# Main.net
KiCad netlist of a schematic drawn in Altium Designer
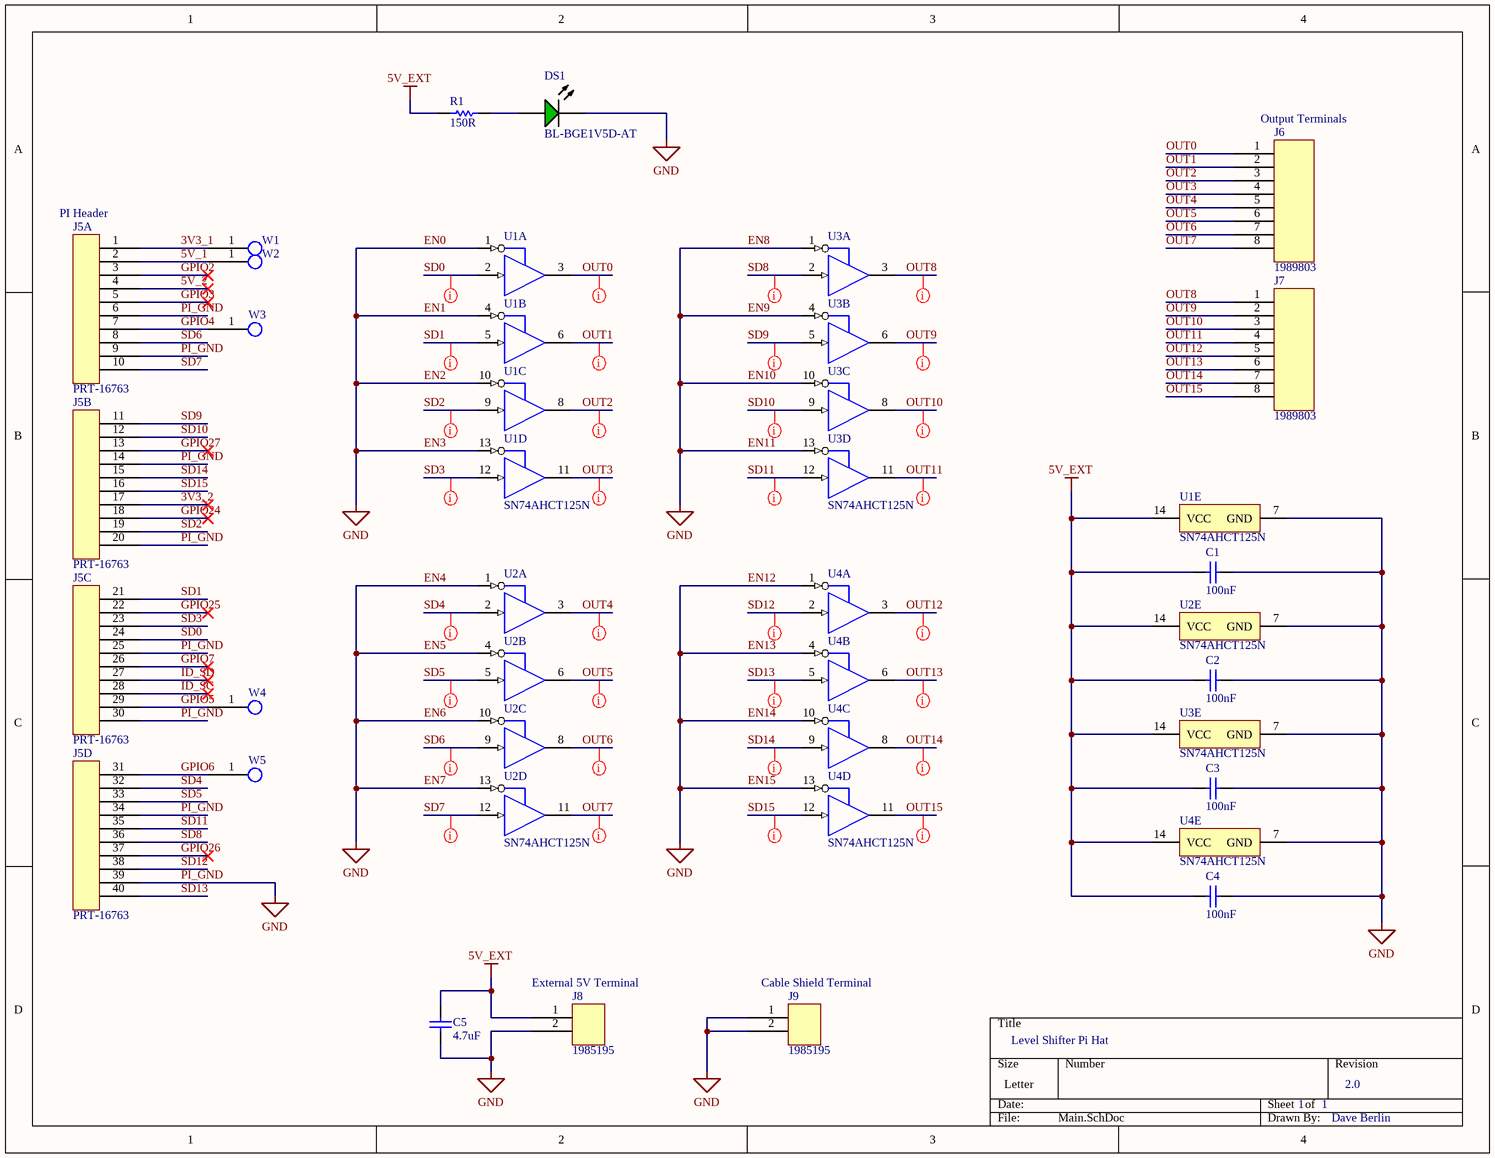
[diagram p0: Main.SchDoc]

(export (version "E")
  (design (tool "Eeschema 10.0.6"))
  (components
    (comp (ref "C1")
      (value "100nF")
      (footprint "FP-CL21-IPC_A")
      (description "CAP CER 0.1UF 50V X7R 0805")
      (fields (field (name "VOLTAGE") "50V") (field (name "TOLERANCE") "10%"))
      (libsource (lib "University of Colorado Boulder") (part "CAP"))
    )
    (comp (ref "C2")
      (value "100nF")
      (footprint "FP-CL21-IPC_A")
      (description "CAP CER 0.1UF 50V X7R 0805")
      (fields (field (name "VOLTAGE") "50V") (field (name "TOLERANCE") "10%"))
      (libsource (lib "University of Colorado Boulder") (part "CAP"))
    )
    (comp (ref "C3")
      (value "100nF")
      (footprint "FP-CL21-IPC_A")
      (description "CAP CER 0.1UF 50V X7R 0805")
      (fields (field (name "VOLTAGE") "50V") (field (name "TOLERANCE") "10%"))
      (libsource (lib "University of Colorado Boulder") (part "CAP"))
    )
    (comp (ref "C4")
      (value "100nF")
      (footprint "FP-CL21-IPC_A")
      (description "CAP CER 0.1UF 50V X7R 0805")
      (fields (field (name "VOLTAGE") "50V") (field (name "TOLERANCE") "10%"))
      (libsource (lib "University of Colorado Boulder") (part "CAP"))
    )
    (comp (ref "C5")
      (value "4.7uF")
      (footprint "FP-CL21-IPC_A")
      (description "CAP CER 4.7UF 25V X5R 0805")
      (fields (field (name "TOLERANCE") "10%") (field (name "Comment") "CL21A475KAQNNNE"))
      (libsource (lib "University of Colorado Boulder") (part "CAP"))
    )
    (comp (ref "DS1")
      (value "BL-BGE1V5D-AT")
      (footprint "LED-2P-2.54-3MM")
      (description "LED Green, 80 mW, 30 mA Max, 200 mcd at 20 mA-40 to 85 degC, 2-Pin THD, RoHS, Bulk")
      (fields (field (name "POWER") "80mW"))
      (libsource (lib "University of Colorado Boulder") (part "LED-GREEN-AK-2"))
    )
    (comp (ref "J5")
      (value "PRT-16763")
      (footprint "PRT-16763-Footprint-1")
      (description "Extended GPIO Female Header - 2x20 Pin (16mm/7.30mm)")
      (libsource (lib "University of Colorado Boulder") (part "PRT-16764-Symbol"))
    )
    (comp (ref "J6")
      (value "1989803")
      (footprint "CONN_1989803_PXC")
      (description "Conn PC Terminal Block 8 POS 2.5mm Solder Thru-Hole 2A")
      (fields (field (name "VOLTAGE") "300V"))
      (libsource (lib "University of Colorado Boulder") (part "Connector-Generic-8-Position"))
    )
    (comp (ref "J7")
      (value "1989803")
      (footprint "CONN_1989803_PXC")
      (description "Conn PC Terminal Block 8 POS 2.5mm Solder Thru-Hole 2A")
      (fields (field (name "VOLTAGE") "300V"))
      (libsource (lib "University of Colorado Boulder") (part "Connector-Generic-8-Position"))
    )
    (comp (ref "J8")
      (value "1985195")
      (footprint "CONN_1985195_PXC")
      (description "Conn PC Terminal Block 2 POS 3.5mm Solder Thru-Hole 8A Cardboard")
      (fields (field (name "VOLTAGE") "300V"))
      (libsource (lib "University of Colorado Boulder") (part "1985195-Symbol-1"))
    )
    (comp (ref "J9")
      (value "1985195")
      (footprint "CONN_1985195_PXC")
      (description "Conn PC Terminal Block 2 POS 3.5mm Solder Thru-Hole 8A Cardboard")
      (fields (field (name "VOLTAGE") "300V"))
      (libsource (lib "University of Colorado Boulder") (part "1985195-Symbol-1"))
    )
    (comp (ref "R1")
      (value "150R")
      (footprint "STA_CF14_STP")
      (description "CF Series 0.25 W 150 Ohm ±5 % 0 to -400 ppm/°C Through Hole Carbon Film Resistor")
      (fields (field (name "TOLERANCE") "5%") (field (name "Comment") "CF14JT150R"))
      (libsource (lib "University of Colorado Boulder") (part "RES"))
    )
    (comp (ref "U1")
      (value "SN74AHCT125N")
      (footprint "N0014A")
      (description "Buffer/Line Driver 4-CH Non-Inverting 3-ST CMOS 14-Pin PDIP Tube")
      (libsource (lib "University of Colorado Boulder") (part "TI-SN74AHCT125-N0014A-14"))
    )
    (comp (ref "U2")
      (value "SN74AHCT125N")
      (footprint "N0014A")
      (description "Buffer/Line Driver 4-CH Non-Inverting 3-ST CMOS 14-Pin PDIP Tube")
      (libsource (lib "University of Colorado Boulder") (part "TI-SN74AHCT125-N0014A-14"))
    )
    (comp (ref "U3")
      (value "SN74AHCT125N")
      (footprint "N0014A")
      (description "Buffer/Line Driver 4-CH Non-Inverting 3-ST CMOS 14-Pin PDIP Tube")
      (libsource (lib "University of Colorado Boulder") (part "TI-SN74AHCT125-N0014A-14"))
    )
    (comp (ref "U4")
      (value "SN74AHCT125N")
      (footprint "N0014A")
      (description "Buffer/Line Driver 4-CH Non-Inverting 3-ST CMOS 14-Pin PDIP Tube")
      (libsource (lib "University of Colorado Boulder") (part "TI-SN74AHCT125-N0014A-14"))
    )
    (comp (ref "W1")
      (value "WIRE-PAD-20AWG")
      (footprint "WIRE-PAD-20AWG")
      (description "38mil / 1.2mm Hole")
      (libsource (lib "University of Colorado Boulder") (part "WIRE-PAD-20AWG-Symbol-1"))
    )
    (comp (ref "W2")
      (value "WIRE-PAD-20AWG")
      (footprint "WIRE-PAD-20AWG")
      (description "38mil / 1.2mm Hole")
      (libsource (lib "University of Colorado Boulder") (part "WIRE-PAD-20AWG-Symbol-1"))
    )
    (comp (ref "W3")
      (value "WIRE-PAD-20AWG")
      (footprint "WIRE-PAD-20AWG")
      (description "38mil / 1.2mm Hole")
      (libsource (lib "University of Colorado Boulder") (part "WIRE-PAD-20AWG-Symbol-1"))
    )
    (comp (ref "W4")
      (value "WIRE-PAD-20AWG")
      (footprint "WIRE-PAD-20AWG")
      (description "38mil / 1.2mm Hole")
      (libsource (lib "University of Colorado Boulder") (part "WIRE-PAD-20AWG-Symbol-1"))
    )
    (comp (ref "W5")
      (value "WIRE-PAD-20AWG")
      (footprint "WIRE-PAD-20AWG")
      (description "38mil / 1.2mm Hole")
      (libsource (lib "University of Colorado Boulder") (part "WIRE-PAD-20AWG-Symbol-1"))
    )
  )
  (nets
    (net (code "1") (name "/3V3_1") (class "Default")
      (node (ref "J5") (pin "1") (pinfunction "1_1") (pintype "passive"))
      (node (ref "W1") (pin "1") (pinfunction "1_1") (pintype "passive"))
    )
    (net (code "2") (name "/3V3_2") (class "Default")
      (node (ref "J5") (pin "17") (pinfunction "17_17") (pintype "passive+no_connect"))
    )
    (net (code "3") (name "/5V_1") (class "Default")
      (node (ref "J5") (pin "2") (pinfunction "2_2") (pintype "passive"))
      (node (ref "W2") (pin "1") (pinfunction "1_1") (pintype "passive"))
    )
    (net (code "4") (name "/5V_2") (class "Default")
      (node (ref "J5") (pin "4") (pinfunction "4_4") (pintype "passive+no_connect"))
    )
    (net (code "5") (name "/GPIO2") (class "Default")
      (node (ref "J5") (pin "3") (pinfunction "3_3") (pintype "passive+no_connect"))
    )
    (net (code "6") (name "/GPIO3") (class "Default")
      (node (ref "J5") (pin "5") (pinfunction "5_5") (pintype "passive+no_connect"))
    )
    (net (code "7") (name "/GPIO4") (class "Default")
      (node (ref "J5") (pin "7") (pinfunction "7_7") (pintype "passive"))
      (node (ref "W3") (pin "1") (pinfunction "1_1") (pintype "passive"))
    )
    (net (code "8") (name "/GPIO5") (class "Default")
      (node (ref "J5") (pin "29") (pinfunction "29_29") (pintype "passive"))
      (node (ref "W4") (pin "1") (pinfunction "1_1") (pintype "passive"))
    )
    (net (code "9") (name "/GPIO6") (class "Default")
      (node (ref "J5") (pin "31") (pinfunction "31_31") (pintype "passive"))
      (node (ref "W5") (pin "1") (pinfunction "1_1") (pintype "passive"))
    )
    (net (code "10") (name "/GPIO7") (class "Default")
      (node (ref "J5") (pin "26") (pinfunction "26_26") (pintype "passive+no_connect"))
    )
    (net (code "11") (name "/GPIO24") (class "Default")
      (node (ref "J5") (pin "18") (pinfunction "18_18") (pintype "passive+no_connect"))
    )
    (net (code "12") (name "/GPIO25") (class "Default")
      (node (ref "J5") (pin "22") (pinfunction "22_22") (pintype "passive+no_connect"))
    )
    (net (code "13") (name "/GPIO26") (class "Default")
      (node (ref "J5") (pin "37") (pinfunction "37_37") (pintype "passive+no_connect"))
    )
    (net (code "14") (name "/GPIO27") (class "Default")
      (node (ref "J5") (pin "13") (pinfunction "13_13") (pintype "passive+no_connect"))
    )
    (net (code "15") (name "/ID_SC") (class "Default")
      (node (ref "J5") (pin "28") (pinfunction "28_28") (pintype "passive+no_connect"))
    )
    (net (code "16") (name "/ID_SD") (class "Default")
      (node (ref "J5") (pin "27") (pinfunction "27_27") (pintype "passive+no_connect"))
    )
    (net (code "17") (name "/OUT0") (class "Default")
      (node (ref "J6") (pin "1") (pinfunction "1_1") (pintype "passive"))
      (node (ref "U1") (pin "3") (pinfunction "1Y_3") (pintype "tri_state"))
    )
    (net (code "18") (name "/OUT1") (class "Default")
      (node (ref "J6") (pin "2") (pinfunction "2_2") (pintype "passive"))
      (node (ref "U1") (pin "6") (pinfunction "2Y_6") (pintype "tri_state"))
    )
    (net (code "19") (name "/OUT2") (class "Default")
      (node (ref "J6") (pin "3") (pinfunction "3_3") (pintype "passive"))
      (node (ref "U1") (pin "8") (pinfunction "3Y_8") (pintype "tri_state"))
    )
    (net (code "20") (name "/OUT3") (class "Default")
      (node (ref "J6") (pin "4") (pinfunction "4_4") (pintype "passive"))
      (node (ref "U1") (pin "11") (pinfunction "4Y_11") (pintype "tri_state"))
    )
    (net (code "21") (name "/OUT4") (class "Default")
      (node (ref "J6") (pin "5") (pinfunction "5_5") (pintype "passive"))
      (node (ref "U2") (pin "3") (pinfunction "1Y_3") (pintype "tri_state"))
    )
    (net (code "22") (name "/OUT5") (class "Default")
      (node (ref "J6") (pin "6") (pinfunction "6_6") (pintype "passive"))
      (node (ref "U2") (pin "6") (pinfunction "2Y_6") (pintype "tri_state"))
    )
    (net (code "23") (name "/OUT6") (class "Default")
      (node (ref "J6") (pin "7") (pinfunction "7_7") (pintype "passive"))
      (node (ref "U2") (pin "8") (pinfunction "3Y_8") (pintype "tri_state"))
    )
    (net (code "24") (name "/OUT7") (class "Default")
      (node (ref "J6") (pin "8") (pinfunction "8_8") (pintype "passive"))
      (node (ref "U2") (pin "11") (pinfunction "4Y_11") (pintype "tri_state"))
    )
    (net (code "25") (name "/OUT8") (class "Default")
      (node (ref "J7") (pin "1") (pinfunction "1_1") (pintype "passive"))
      (node (ref "U3") (pin "3") (pinfunction "1Y_3") (pintype "tri_state"))
    )
    (net (code "26") (name "/OUT9") (class "Default")
      (node (ref "J7") (pin "2") (pinfunction "2_2") (pintype "passive"))
      (node (ref "U3") (pin "6") (pinfunction "2Y_6") (pintype "tri_state"))
    )
    (net (code "27") (name "/OUT10") (class "Default")
      (node (ref "J7") (pin "3") (pinfunction "3_3") (pintype "passive"))
      (node (ref "U3") (pin "8") (pinfunction "3Y_8") (pintype "tri_state"))
    )
    (net (code "28") (name "/OUT11") (class "Default")
      (node (ref "J7") (pin "4") (pinfunction "4_4") (pintype "passive"))
      (node (ref "U3") (pin "11") (pinfunction "4Y_11") (pintype "tri_state"))
    )
    (net (code "29") (name "/OUT12") (class "Default")
      (node (ref "J7") (pin "5") (pinfunction "5_5") (pintype "passive"))
      (node (ref "U4") (pin "3") (pinfunction "1Y_3") (pintype "tri_state"))
    )
    (net (code "30") (name "/OUT13") (class "Default")
      (node (ref "J7") (pin "6") (pinfunction "6_6") (pintype "passive"))
      (node (ref "U4") (pin "6") (pinfunction "2Y_6") (pintype "tri_state"))
    )
    (net (code "31") (name "/OUT14") (class "Default")
      (node (ref "J7") (pin "7") (pinfunction "7_7") (pintype "passive"))
      (node (ref "U4") (pin "8") (pinfunction "3Y_8") (pintype "tri_state"))
    )
    (net (code "32") (name "/OUT15") (class "Default")
      (node (ref "J7") (pin "8") (pinfunction "8_8") (pintype "passive"))
      (node (ref "U4") (pin "11") (pinfunction "4Y_11") (pintype "tri_state"))
    )
    (net (code "33") (name "/SD0") (class "Default")
      (node (ref "J5") (pin "24") (pinfunction "24_24") (pintype "passive"))
      (node (ref "U1") (pin "2") (pinfunction "1A_2") (pintype "input"))
    )
    (net (code "34") (name "/SD1") (class "Default")
      (node (ref "J5") (pin "21") (pinfunction "21_21") (pintype "passive"))
      (node (ref "U1") (pin "5") (pinfunction "2A_5") (pintype "input"))
    )
    (net (code "35") (name "/SD2") (class "Default")
      (node (ref "J5") (pin "19") (pinfunction "19_19") (pintype "passive"))
      (node (ref "U1") (pin "9") (pinfunction "3A_9") (pintype "input"))
    )
    (net (code "36") (name "/SD3") (class "Default")
      (node (ref "J5") (pin "23") (pinfunction "23_23") (pintype "passive"))
      (node (ref "U1") (pin "12") (pinfunction "4A_12") (pintype "input"))
    )
    (net (code "37") (name "/SD4") (class "Default")
      (node (ref "J5") (pin "32") (pinfunction "32_32") (pintype "passive"))
      (node (ref "U2") (pin "2") (pinfunction "1A_2") (pintype "input"))
    )
    (net (code "38") (name "/SD5") (class "Default")
      (node (ref "J5") (pin "33") (pinfunction "33_33") (pintype "passive"))
      (node (ref "U2") (pin "5") (pinfunction "2A_5") (pintype "input"))
    )
    (net (code "39") (name "/SD6") (class "Default")
      (node (ref "J5") (pin "8") (pinfunction "8_8") (pintype "passive"))
      (node (ref "U2") (pin "9") (pinfunction "3A_9") (pintype "input"))
    )
    (net (code "40") (name "/SD7") (class "Default")
      (node (ref "J5") (pin "10") (pinfunction "10_10") (pintype "passive"))
      (node (ref "U2") (pin "12") (pinfunction "4A_12") (pintype "input"))
    )
    (net (code "41") (name "/SD8") (class "Default")
      (node (ref "J5") (pin "36") (pinfunction "36_36") (pintype "passive"))
      (node (ref "U3") (pin "2") (pinfunction "1A_2") (pintype "input"))
    )
    (net (code "42") (name "/SD9") (class "Default")
      (node (ref "J5") (pin "11") (pinfunction "11_11") (pintype "passive"))
      (node (ref "U3") (pin "5") (pinfunction "2A_5") (pintype "input"))
    )
    (net (code "43") (name "/SD10") (class "Default")
      (node (ref "J5") (pin "12") (pinfunction "12_12") (pintype "passive"))
      (node (ref "U3") (pin "9") (pinfunction "3A_9") (pintype "input"))
    )
    (net (code "44") (name "/SD11") (class "Default")
      (node (ref "J5") (pin "35") (pinfunction "35_35") (pintype "passive"))
      (node (ref "U3") (pin "12") (pinfunction "4A_12") (pintype "input"))
    )
    (net (code "45") (name "/SD12") (class "Default")
      (node (ref "J5") (pin "38") (pinfunction "38_38") (pintype "passive"))
      (node (ref "U4") (pin "2") (pinfunction "1A_2") (pintype "input"))
    )
    (net (code "46") (name "/SD13") (class "Default")
      (node (ref "J5") (pin "40") (pinfunction "40_40") (pintype "passive"))
      (node (ref "U4") (pin "5") (pinfunction "2A_5") (pintype "input"))
    )
    (net (code "47") (name "/SD14") (class "Default")
      (node (ref "J5") (pin "15") (pinfunction "15_15") (pintype "passive"))
      (node (ref "U4") (pin "9") (pinfunction "3A_9") (pintype "input"))
    )
    (net (code "48") (name "/SD15") (class "Default")
      (node (ref "J5") (pin "16") (pinfunction "16_16") (pintype "passive"))
      (node (ref "U4") (pin "12") (pinfunction "4A_12") (pintype "input"))
    )
    (net (code "49") (name "5V_EXT") (class "Default")
      (node (ref "C1") (pin "1") (pinfunction "1_1") (pintype "passive"))
      (node (ref "C2") (pin "1") (pinfunction "1_1") (pintype "passive"))
      (node (ref "C3") (pin "1") (pinfunction "1_1") (pintype "passive"))
      (node (ref "C4") (pin "1") (pinfunction "1_1") (pintype "passive"))
      (node (ref "C5") (pin "2") (pinfunction "2_2") (pintype "passive"))
      (node (ref "J8") (pin "1") (pinfunction "1_1") (pintype "passive"))
      (node (ref "R1") (pin "1") (pinfunction "1_1") (pintype "passive"))
      (node (ref "U1") (pin "14") (pinfunction "VCC_14") (pintype "power_in"))
      (node (ref "U2") (pin "14") (pinfunction "VCC_14") (pintype "power_in"))
      (node (ref "U3") (pin "14") (pinfunction "VCC_14") (pintype "power_in"))
      (node (ref "U4") (pin "14") (pinfunction "VCC_14") (pintype "power_in"))
    )
    (net (code "50") (name "GND") (class "Default")
      (node (ref "C1") (pin "2") (pinfunction "2_2") (pintype "passive"))
      (node (ref "C2") (pin "2") (pinfunction "2_2") (pintype "passive"))
      (node (ref "C3") (pin "2") (pinfunction "2_2") (pintype "passive"))
      (node (ref "C4") (pin "2") (pinfunction "2_2") (pintype "passive"))
      (node (ref "C5") (pin "1") (pinfunction "1_1") (pintype "passive"))
      (node (ref "DS1") (pin "2") (pinfunction "K_2") (pintype "passive"))
      (node (ref "J5") (pin "14") (pinfunction "14_14") (pintype "passive"))
      (node (ref "J5") (pin "20") (pinfunction "20_20") (pintype "passive"))
      (node (ref "J5") (pin "25") (pinfunction "25_25") (pintype "passive"))
      (node (ref "J5") (pin "30") (pinfunction "30_30") (pintype "passive"))
      (node (ref "J5") (pin "34") (pinfunction "34_34") (pintype "passive"))
      (node (ref "J5") (pin "39") (pinfunction "39_39") (pintype "passive"))
      (node (ref "J5") (pin "6") (pinfunction "6_6") (pintype "passive"))
      (node (ref "J5") (pin "9") (pinfunction "9_9") (pintype "passive"))
      (node (ref "J8") (pin "2") (pinfunction "2_2") (pintype "passive"))
      (node (ref "J9") (pin "1") (pinfunction "1_1") (pintype "passive"))
      (node (ref "J9") (pin "2") (pinfunction "2_2") (pintype "passive"))
      (node (ref "U1") (pin "1") (pinfunction "1~{OE}_1") (pintype "input"))
      (node (ref "U1") (pin "10") (pinfunction "3~{OE}_10") (pintype "input"))
      (node (ref "U1") (pin "13") (pinfunction "4~{OE}_13") (pintype "input"))
      (node (ref "U1") (pin "4") (pinfunction "2~{OE}_4") (pintype "input"))
      (node (ref "U1") (pin "7") (pinfunction "GND_7") (pintype "power_in"))
      (node (ref "U2") (pin "1") (pinfunction "1~{OE}_1") (pintype "input"))
      (node (ref "U2") (pin "10") (pinfunction "3~{OE}_10") (pintype "input"))
      (node (ref "U2") (pin "13") (pinfunction "4~{OE}_13") (pintype "input"))
      (node (ref "U2") (pin "4") (pinfunction "2~{OE}_4") (pintype "input"))
      (node (ref "U2") (pin "7") (pinfunction "GND_7") (pintype "power_in"))
      (node (ref "U3") (pin "1") (pinfunction "1~{OE}_1") (pintype "input"))
      (node (ref "U3") (pin "10") (pinfunction "3~{OE}_10") (pintype "input"))
      (node (ref "U3") (pin "13") (pinfunction "4~{OE}_13") (pintype "input"))
      (node (ref "U3") (pin "4") (pinfunction "2~{OE}_4") (pintype "input"))
      (node (ref "U3") (pin "7") (pinfunction "GND_7") (pintype "power_in"))
      (node (ref "U4") (pin "1") (pinfunction "1~{OE}_1") (pintype "input"))
      (node (ref "U4") (pin "10") (pinfunction "3~{OE}_10") (pintype "input"))
      (node (ref "U4") (pin "13") (pinfunction "4~{OE}_13") (pintype "input"))
      (node (ref "U4") (pin "4") (pinfunction "2~{OE}_4") (pintype "input"))
      (node (ref "U4") (pin "7") (pinfunction "GND_7") (pintype "power_in"))
    )
    (net (code "51") (name "Net-(DS1-A)") (class "Default")
      (node (ref "DS1") (pin "1") (pinfunction "A_1") (pintype "passive"))
      (node (ref "R1") (pin "2") (pinfunction "2_2") (pintype "passive"))
    )
  )
)
